# dengenver4_0.net
KiCad netlist of a schematic drawn in EAGLE
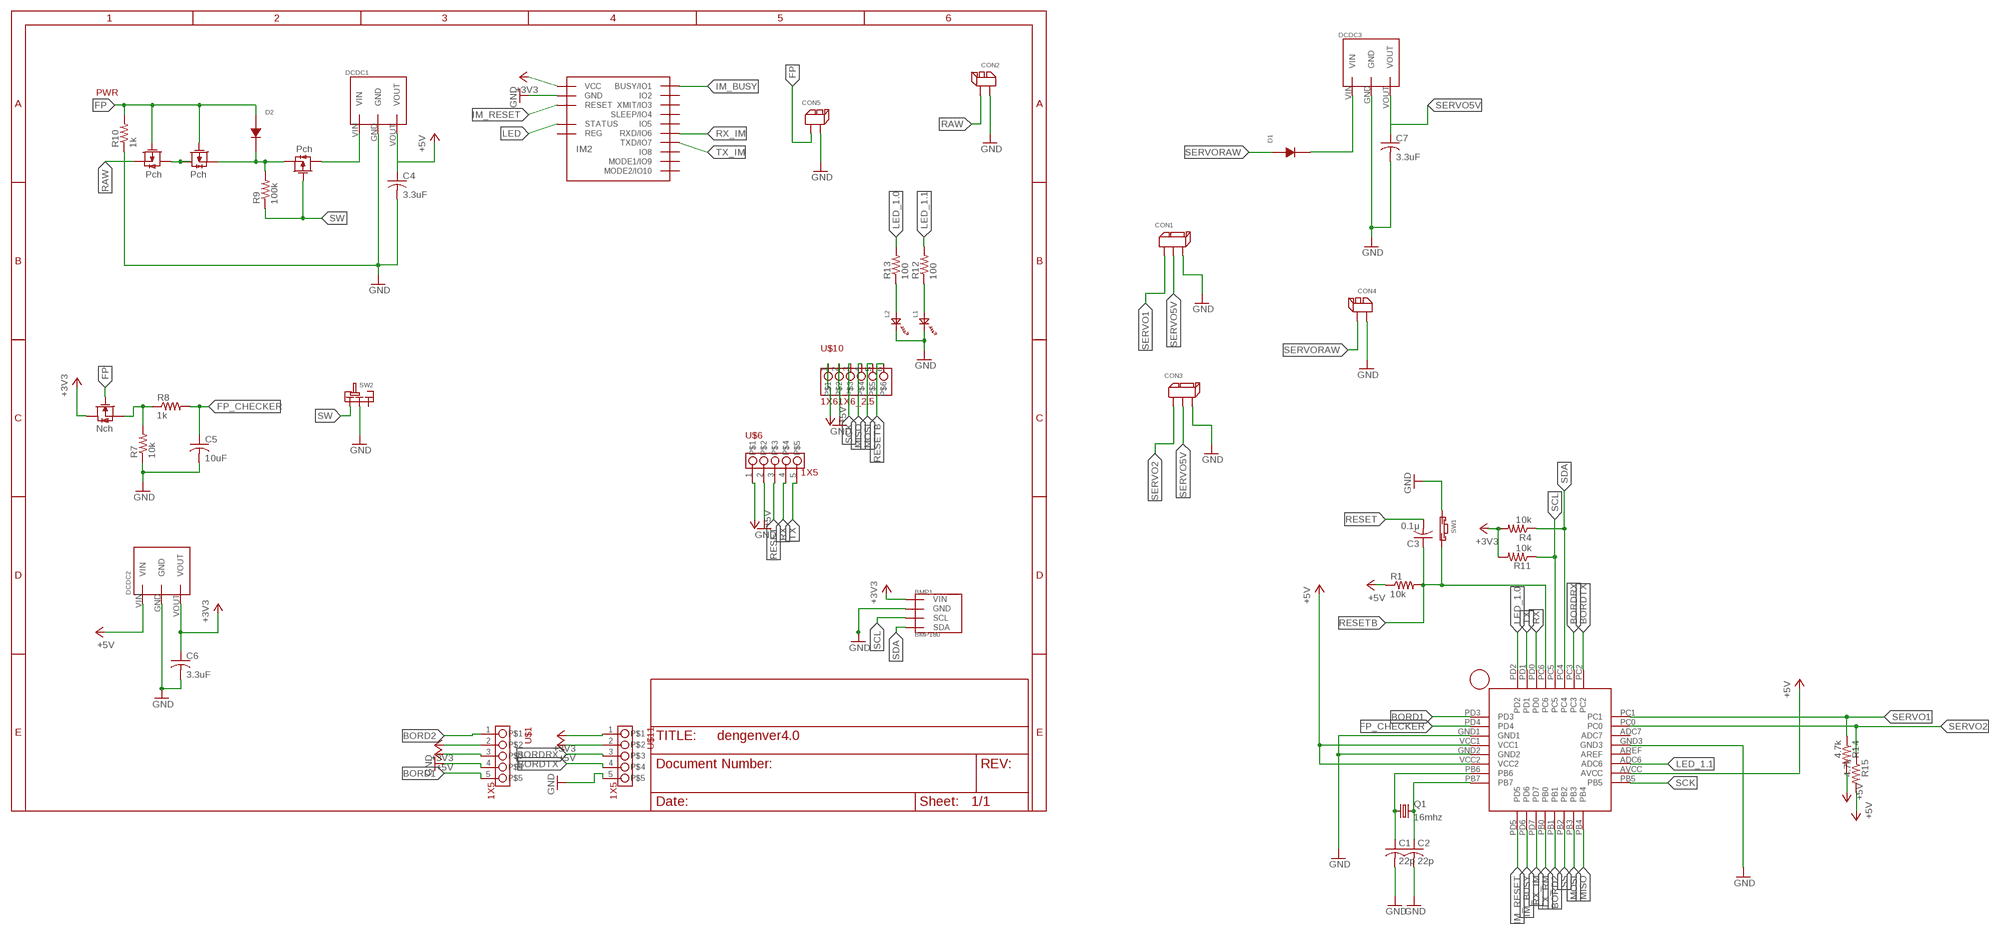
[diagram p0: schematic, sheet 1]

(export (version "E")
  (design (tool "Eeschema 10.0.6"))
  (components
    (comp (ref "BMP1")
      (value "BMP180")
      (footprint "eagle-import:GY-68")
      (libsource (lib "eagle-import") (part "BMP180"))
    )
    (comp (ref "C1")
      (value "22p")
      (footprint "eagle-import:C1608")
      (libsource (lib "eagle-import") (part "C-USC1608"))
    )
    (comp (ref "C2")
      (value "22p")
      (footprint "eagle-import:C1608")
      (libsource (lib "eagle-import") (part "C-USC1608"))
    )
    (comp (ref "C3")
      (value "0.1μ")
      (footprint "eagle-import:C1608")
      (libsource (lib "eagle-import") (part "C-USC1608"))
    )
    (comp (ref "C4")
      (value "3.3uF")
      (footprint "eagle-import:C1608")
      (libsource (lib "eagle-import") (part "C-USC1608"))
    )
    (comp (ref "C5")
      (value "10uF")
      (footprint "eagle-import:C1608")
      (libsource (lib "eagle-import") (part "C-USC1608"))
    )
    (comp (ref "C6")
      (value "3.3uF")
      (footprint "eagle-import:C1608")
      (libsource (lib "eagle-import") (part "C-USC1608"))
    )
    (comp (ref "C7")
      (value "3.3uF")
      (footprint "eagle-import:C0603")
      (libsource (lib "eagle-import") (part "C-USC0603"))
    )
    (comp (ref "CON1")
      (value "3PIN")
      (footprint "eagle-import:3PIN")
      (libsource (lib "eagle-import") (part "3PIN"))
    )
    (comp (ref "CON2")
      (value "2PIN")
      (footprint "eagle-import:2PIN")
      (libsource (lib "eagle-import") (part "2PIN"))
    )
    (comp (ref "CON3")
      (value "3PIN")
      (footprint "eagle-import:3PIN")
      (libsource (lib "eagle-import") (part "3PIN"))
    )
    (comp (ref "CON4")
      (value "2PIN")
      (footprint "eagle-import:2PIN")
      (libsource (lib "eagle-import") (part "2PIN"))
    )
    (comp (ref "CON5")
      (value "2PIN")
      (footprint "eagle-import:2PIN")
      (libsource (lib "eagle-import") (part "2PIN"))
    )
    (comp (ref "D1")
      (value "1W4148W")
      (footprint "eagle-import:SOD-123")
      (libsource (lib "eagle-import") (part "1W4148W"))
    )
    (comp (ref "D2")
      (value "1W4148W")
      (footprint "eagle-import:SOD-123")
      (libsource (lib "eagle-import") (part "1W4148W"))
    )
    (comp (ref "DCDC1")
      (value "5V1A_M78AR05-1")
      (footprint "eagle-import:5V1A_M78AR05-1")
      (libsource (lib "eagle-import") (part "5V1A_M78AR05-1"))
    )
    (comp (ref "DCDC2")
      (value "3.3V1A_M78AR033-1")
      (footprint "eagle-import:3.3V1A_M78AR033-1")
      (libsource (lib "eagle-import") (part "3.3V1A_M78AR033-1"))
    )
    (comp (ref "DCDC3")
      (value "5V1A_M78AR05-1")
      (footprint "eagle-import:5V1A_M78AR05-1")
      (libsource (lib "eagle-import") (part "5V1A_M78AR05-1"))
    )
    (comp (ref "IM2")
      (value "IM920_IM920C")
      (footprint "eagle-import:IM920_IM920C")
      (libsource (lib "eagle-import") (part "IM920_IM920C"))
    )
    (comp (ref "L1")
      (value "OSXX1608C1A")
      (footprint "eagle-import:OSXX1608C1A")
      (libsource (lib "eagle-import") (part "OSXX1608C1A"))
    )
    (comp (ref "L2")
      (value "OSXX1608C1A")
      (footprint "eagle-import:OSXX1608C1A")
      (libsource (lib "eagle-import") (part "OSXX1608C1A"))
    )
    (comp (ref "Q1")
      (value "16mhz")
      (footprint "eagle-import:HC49UP")
      (libsource (lib "eagle-import") (part "CRYSTALHC49UP"))
    )
    (comp (ref "R1")
      (value "10k")
      (footprint "eagle-import:R0603")
      (libsource (lib "eagle-import") (part "R-US_R0603"))
    )
    (comp (ref "R4")
      (value "10k")
      (footprint "eagle-import:R0603")
      (libsource (lib "eagle-import") (part "R-US_R0603"))
    )
    (comp (ref "R7")
      (value "10k")
      (footprint "eagle-import:R0603")
      (libsource (lib "eagle-import") (part "R-US_R0603"))
    )
    (comp (ref "R8")
      (value "1k")
      (footprint "eagle-import:R0603")
      (libsource (lib "eagle-import") (part "R-US_R0603"))
    )
    (comp (ref "R9")
      (value "100k")
      (footprint "eagle-import:R0603")
      (libsource (lib "eagle-import") (part "R-US_R0603"))
    )
    (comp (ref "R10")
      (value "1k")
      (footprint "eagle-import:R0603")
      (libsource (lib "eagle-import") (part "R-US_R0603"))
    )
    (comp (ref "R11")
      (value "10k")
      (footprint "eagle-import:R0603")
      (libsource (lib "eagle-import") (part "R-US_R0603"))
    )
    (comp (ref "R12")
      (value "100")
      (footprint "eagle-import:R0603")
      (libsource (lib "eagle-import") (part "R-US_R0603"))
    )
    (comp (ref "R13")
      (value "100")
      (footprint "eagle-import:R0603")
      (libsource (lib "eagle-import") (part "R-US_R0603"))
    )
    (comp (ref "R14")
      (value "4.7k")
      (footprint "eagle-import:R0603")
      (libsource (lib "eagle-import") (part "R-US_R0603"))
    )
    (comp (ref "R15")
      (value "4.7k")
      (footprint "eagle-import:R0603")
      (libsource (lib "eagle-import") (part "R-US_R0603"))
    )
    (comp (ref "SW1")
      (value "TVAF06-A020B-R")
      (footprint "eagle-import:TVAF06-A020B-R")
      (libsource (lib "eagle-import") (part "TVAF06-A020B-R"))
    )
    (comp (ref "SW2")
      (value "SRIDE_SWITCH")
      (footprint "eagle-import:SRIDE_SWITCH")
      (libsource (lib "eagle-import") (part "SRIDE_SWITCH"))
    )
    (comp (ref "U$1")
      (value "1X5")
      (footprint "eagle-import:HDRVR5W64P254_1X5_1310X250X865B")
      (libsource (lib "eagle-import") (part "1X5"))
    )
    (comp (ref "U$2")
      (value "2SJ681-PCH")
      (footprint "eagle-import:2SJ681")
      (libsource (lib "eagle-import") (part "2SJ681-PCH"))
    )
    (comp (ref "U$3")
      (value "2SK4017-NCH")
      (footprint "eagle-import:2SK4017")
      (libsource (lib "eagle-import") (part "2SK4017-NCH"))
    )
    (comp (ref "U$4")
      (value "2SJ681-PCH")
      (footprint "eagle-import:2SJ681")
      (libsource (lib "eagle-import") (part "2SJ681-PCH"))
    )
    (comp (ref "U$5")
      (value "2SJ681-PCH")
      (footprint "eagle-import:2SJ681")
      (libsource (lib "eagle-import") (part "2SJ681-PCH"))
    )
    (comp (ref "U$6")
      (value "1X5")
      (footprint "eagle-import:HDRVR5W64P254_1X5_1310X250X865B")
      (libsource (lib "eagle-import") (part "1X5"))
    )
    (comp (ref "U$8")
      (value "ATMEGA328P-AU")
      (footprint "eagle-import:QFP80P900X900X120-32N")
      (libsource (lib "eagle-import") (part "ATMEGA328P-AU"))
    )
    (comp (ref "U$10")
      (value "1X61X6_2.5")
      (footprint "eagle-import:HDRVR6W64P254_1X6_1564X250X865B")
      (libsource (lib "eagle-import") (part "1X61X6_2.5"))
    )
    (comp (ref "U$11")
      (value "1X5")
      (footprint "eagle-import:HDRVR5W64P254_1X5_1310X250X865B")
      (libsource (lib "eagle-import") (part "1X5"))
    )
  )
  (nets
    (net (code "1") (name "+3V3") (class "Default")
      (node (ref "BMP1") (pin "P1") (pinfunction "VIN_P1") (pintype "bidirectional"))
      (node (ref "C6") (pin "1") (pinfunction "1_1") (pintype "passive"))
      (node (ref "DCDC2") (pin "VOUT") (pinfunction "VOUT_VOUT") (pintype "bidirectional"))
      (node (ref "IM2") (pin "$P17") (pinfunction "VCC_$P17") (pintype "bidirectional"))
      (node (ref "R11") (pin "2") (pinfunction "2_2") (pintype "passive"))
      (node (ref "R4") (pin "2") (pinfunction "2_2") (pintype "passive"))
      (node (ref "U$1") (pin "2") (pinfunction "P$2_2") (pintype "bidirectional"))
      (node (ref "U$11") (pin "1") (pinfunction "P$1_1") (pintype "bidirectional"))
      (node (ref "U$3") (pin "DRAIN") (pinfunction "DRAIN_DRAIN") (pintype "bidirectional"))
    )
    (net (code "2") (name "+5V") (class "Default")
      (node (ref "C4") (pin "1") (pinfunction "1_1") (pintype "passive"))
      (node (ref "DCDC1") (pin "VOUT") (pinfunction "VOUT_VOUT") (pintype "bidirectional"))
      (node (ref "DCDC2") (pin "VIN") (pinfunction "VIN_VIN") (pintype "bidirectional"))
      (node (ref "R1") (pin "1") (pinfunction "1_1") (pintype "passive"))
      (node (ref "R14") (pin "2") (pinfunction "2_2") (pintype "passive"))
      (node (ref "R15") (pin "2") (pinfunction "2_2") (pintype "passive"))
      (node (ref "U$1") (pin "3") (pinfunction "P$3_3") (pintype "bidirectional"))
      (node (ref "U$10") (pin "1") (pinfunction "P$1_1") (pintype "bidirectional"))
      (node (ref "U$11") (pin "2") (pinfunction "P$2_2") (pintype "bidirectional"))
      (node (ref "U$6") (pin "1") (pinfunction "P$1_1") (pintype "bidirectional"))
      (node (ref "U$8") (pin "AVCC") (pinfunction "AVCC_AVCC") (pintype "bidirectional"))
      (node (ref "U$8") (pin "VCC1") (pinfunction "VCC1_VCC1") (pintype "bidirectional"))
      (node (ref "U$8") (pin "VCC2") (pinfunction "VCC2_VCC2") (pintype "bidirectional"))
    )
    (net (code "3") (name "BORD1") (class "Default")
      (node (ref "U$1") (pin "5") (pinfunction "P$5_5") (pintype "bidirectional"))
      (node (ref "U$8") (pin "PD3") (pinfunction "PD3_PD3") (pintype "bidirectional"))
    )
    (net (code "4") (name "BORD2") (class "Default")
      (node (ref "U$1") (pin "1") (pinfunction "P$1_1") (pintype "bidirectional"))
      (node (ref "U$8") (pin "PB1") (pinfunction "PB1_PB1") (pintype "bidirectional"))
    )
    (net (code "5") (name "BORDRX") (class "Default")
      (node (ref "U$11") (pin "3") (pinfunction "P$3_3") (pintype "bidirectional"))
      (node (ref "U$8") (pin "PC3") (pinfunction "PC3_PC3") (pintype "bidirectional"))
    )
    (net (code "6") (name "BORDTX") (class "Default")
      (node (ref "U$11") (pin "4") (pinfunction "P$4_4") (pintype "bidirectional"))
      (node (ref "U$8") (pin "PC2") (pinfunction "PC2_PC2") (pintype "bidirectional"))
    )
    (net (code "7") (name "FP") (class "Default")
      (node (ref "CON5") (pin "P$1") (pinfunction "P$1_P$1") (pintype "bidirectional"))
      (node (ref "D2") (pin "C") (pinfunction "C_C") (pintype "bidirectional"))
      (node (ref "R10") (pin "2") (pinfunction "2_2") (pintype "passive"))
      (node (ref "U$2") (pin "GATE") (pinfunction "GATE_GATE") (pintype "bidirectional"))
      (node (ref "U$3") (pin "GATE") (pinfunction "GATE_GATE") (pintype "bidirectional"))
      (node (ref "U$4") (pin "GATE") (pinfunction "GATE_GATE") (pintype "bidirectional"))
    )
    (net (code "8") (name "FP_CHECKER") (class "Default")
      (node (ref "C5") (pin "1") (pinfunction "1_1") (pintype "passive"))
      (node (ref "R8") (pin "2") (pinfunction "2_2") (pintype "passive"))
      (node (ref "U$8") (pin "PD4") (pinfunction "PD4_PD4") (pintype "bidirectional"))
    )
    (net (code "9") (name "GND") (class "Default")
      (node (ref "BMP1") (pin "P2") (pinfunction "GND_P2") (pintype "bidirectional"))
      (node (ref "C1") (pin "2") (pinfunction "2_2") (pintype "passive"))
      (node (ref "C2") (pin "2") (pinfunction "2_2") (pintype "passive"))
      (node (ref "C4") (pin "2") (pinfunction "2_2") (pintype "passive"))
      (node (ref "C5") (pin "2") (pinfunction "2_2") (pintype "passive"))
      (node (ref "C6") (pin "2") (pinfunction "2_2") (pintype "passive"))
      (node (ref "C7") (pin "2") (pinfunction "2_2") (pintype "passive"))
      (node (ref "CON1") (pin "P$3") (pinfunction "P$3_P$3") (pintype "bidirectional"))
      (node (ref "CON2") (pin "P$1") (pinfunction "P$1_P$1") (pintype "bidirectional"))
      (node (ref "CON3") (pin "P$3") (pinfunction "P$3_P$3") (pintype "bidirectional"))
      (node (ref "CON4") (pin "P$1") (pinfunction "P$1_P$1") (pintype "bidirectional"))
      (node (ref "CON5") (pin "P$2") (pinfunction "P$2_P$2") (pintype "bidirectional"))
      (node (ref "DCDC1") (pin "GND") (pinfunction "GND_GND") (pintype "bidirectional"))
      (node (ref "DCDC2") (pin "GND") (pinfunction "GND_GND") (pintype "bidirectional"))
      (node (ref "DCDC3") (pin "GND") (pinfunction "GND_GND") (pintype "bidirectional"))
      (node (ref "IM2") (pin "$P18") (pinfunction "GND_$P18") (pintype "bidirectional"))
      (node (ref "L1") (pin "CT") (pinfunction "CT_CT") (pintype "bidirectional"))
      (node (ref "L2") (pin "CT") (pinfunction "CT_CT") (pintype "bidirectional"))
      (node (ref "R10") (pin "1") (pinfunction "1_1") (pintype "passive"))
      (node (ref "R7") (pin "1") (pinfunction "1_1") (pintype "passive"))
      (node (ref "SW1") (pin "P$1") (pinfunction "P$1_P$1") (pintype "bidirectional"))
      (node (ref "SW2") (pin "LR") (pinfunction "LR_LR") (pintype "bidirectional"))
      (node (ref "U$1") (pin "4") (pinfunction "P$4_4") (pintype "bidirectional"))
      (node (ref "U$10") (pin "2") (pinfunction "P$2_2") (pintype "bidirectional"))
      (node (ref "U$11") (pin "5") (pinfunction "P$5_5") (pintype "bidirectional"))
      (node (ref "U$6") (pin "2") (pinfunction "P$2_2") (pintype "bidirectional"))
      (node (ref "U$8") (pin "GND1") (pinfunction "GND1_GND1") (pintype "bidirectional"))
      (node (ref "U$8") (pin "GND2") (pinfunction "GND2_GND2") (pintype "bidirectional"))
      (node (ref "U$8") (pin "GND3") (pinfunction "GND3_GND3") (pintype "bidirectional"))
    )
    (net (code "10") (name "IM_BUSY") (class "Default")
      (node (ref "IM2") (pin "$P1") (pinfunction "BUSY/IO1_$P1") (pintype "bidirectional"))
      (node (ref "U$8") (pin "PD6") (pinfunction "PD6_PD6") (pintype "bidirectional"))
    )
    (net (code "11") (name "IM_RESET") (class "Default")
      (node (ref "IM2") (pin "$P19") (pinfunction "RESET_$P19") (pintype "bidirectional"))
      (node (ref "U$8") (pin "PD5") (pinfunction "PD5_PD5") (pintype "bidirectional"))
    )
    (net (code "12") (name "LED") (class "Default")
      (node (ref "IM2") (pin "$P15") (pinfunction "STATUS_$P15") (pintype "bidirectional"))
    )
    (net (code "13") (name "LED_1.0") (class "Default")
      (node (ref "R13") (pin "2") (pinfunction "2_2") (pintype "passive"))
      (node (ref "U$8") (pin "PD2") (pinfunction "PD2_PD2") (pintype "bidirectional"))
    )
    (net (code "14") (name "LED_1.1") (class "Default")
      (node (ref "R12") (pin "2") (pinfunction "2_2") (pintype "passive"))
      (node (ref "U$8") (pin "ADC6") (pinfunction "ADC6_ADC6") (pintype "bidirectional"))
    )
    (net (code "15") (name "MISO") (class "Default")
      (node (ref "U$10") (pin "4") (pinfunction "P$4_4") (pintype "bidirectional"))
      (node (ref "U$8") (pin "PB4") (pinfunction "PB4_PB4") (pintype "bidirectional"))
    )
    (net (code "16") (name "MOSI") (class "Default")
      (node (ref "U$10") (pin "5") (pinfunction "P$5_5") (pintype "bidirectional"))
      (node (ref "U$8") (pin "PB3") (pinfunction "PB3_PB3") (pintype "bidirectional"))
    )
    (net (code "17") (name "Net-(C1-Pad1)") (class "Default")
      (node (ref "C1") (pin "1") (pinfunction "1_1") (pintype "passive"))
      (node (ref "Q1") (pin "1") (pinfunction "1_1") (pintype "passive"))
      (node (ref "U$8") (pin "PB6") (pinfunction "PB6_PB6") (pintype "bidirectional"))
    )
    (net (code "18") (name "Net-(C2-Pad1)") (class "Default")
      (node (ref "C2") (pin "1") (pinfunction "1_1") (pintype "passive"))
      (node (ref "Q1") (pin "2") (pinfunction "2_2") (pintype "passive"))
      (node (ref "U$8") (pin "PB7") (pinfunction "PB7_PB7") (pintype "bidirectional"))
    )
    (net (code "19") (name "Net-(D2-PadA)") (class "Default")
      (node (ref "D2") (pin "A") (pinfunction "A_A") (pintype "bidirectional"))
      (node (ref "R9") (pin "2") (pinfunction "2_2") (pintype "passive"))
      (node (ref "U$4") (pin "SOURCE") (pinfunction "SOURCE_SOURCE") (pintype "bidirectional"))
      (node (ref "U$5") (pin "SOURCE") (pinfunction "SOURCE_SOURCE") (pintype "bidirectional"))
    )
    (net (code "20") (name "Net-(DCDC1-PadVIN)") (class "Default")
      (node (ref "DCDC1") (pin "VIN") (pinfunction "VIN_VIN") (pintype "bidirectional"))
      (node (ref "U$5") (pin "DRAIN") (pinfunction "DRAIN_DRAIN") (pintype "bidirectional"))
    )
    (net (code "21") (name "Net-(L1-PadAN)") (class "Default")
      (node (ref "L1") (pin "AN") (pinfunction "AN_AN") (pintype "bidirectional"))
      (node (ref "R12") (pin "1") (pinfunction "1_1") (pintype "passive"))
    )
    (net (code "22") (name "Net-(L2-PadAN)") (class "Default")
      (node (ref "L2") (pin "AN") (pinfunction "AN_AN") (pintype "bidirectional"))
      (node (ref "R13") (pin "1") (pinfunction "1_1") (pintype "passive"))
    )
    (net (code "23") (name "Net-(R7-Pad2)") (class "Default")
      (node (ref "R7") (pin "2") (pinfunction "2_2") (pintype "passive"))
      (node (ref "R8") (pin "1") (pinfunction "1_1") (pintype "passive"))
      (node (ref "U$3") (pin "SOURCE") (pinfunction "SOURCE_SOURCE") (pintype "bidirectional"))
    )
    (net (code "24") (name "Net-(U$2-PadDRAIN)") (class "Default")
      (node (ref "U$2") (pin "DRAIN") (pinfunction "DRAIN_DRAIN") (pintype "bidirectional"))
      (node (ref "U$4") (pin "DRAIN") (pinfunction "DRAIN_DRAIN") (pintype "bidirectional"))
    )
    (net (code "25") (name "RAW") (class "Default")
      (node (ref "CON2") (pin "P$2") (pinfunction "P$2_P$2") (pintype "bidirectional"))
      (node (ref "U$2") (pin "SOURCE") (pinfunction "SOURCE_SOURCE") (pintype "bidirectional"))
    )
    (net (code "26") (name "RESET") (class "Default")
      (node (ref "C3") (pin "2") (pinfunction "2_2") (pintype "passive"))
      (node (ref "U$6") (pin "3") (pinfunction "P$3_3") (pintype "bidirectional"))
    )
    (net (code "27") (name "RESETB") (class "Default")
      (node (ref "C3") (pin "1") (pinfunction "1_1") (pintype "passive"))
      (node (ref "R1") (pin "2") (pinfunction "2_2") (pintype "passive"))
      (node (ref "SW1") (pin "P$2") (pinfunction "P$2_P$2") (pintype "bidirectional"))
      (node (ref "U$10") (pin "6") (pinfunction "P$6_6") (pintype "bidirectional"))
      (node (ref "U$8") (pin "PC6") (pinfunction "PC6_PC6") (pintype "bidirectional"))
    )
    (net (code "28") (name "RX") (class "Default")
      (node (ref "U$6") (pin "4") (pinfunction "P$4_4") (pintype "bidirectional"))
      (node (ref "U$8") (pin "PD0") (pinfunction "PD0_PD0") (pintype "bidirectional"))
    )
    (net (code "29") (name "RX_IM") (class "Default")
      (node (ref "IM2") (pin "$P6") (pinfunction "RXD/IO6_$P6") (pintype "bidirectional"))
      (node (ref "U$8") (pin "PD7") (pinfunction "PD7_PD7") (pintype "bidirectional"))
    )
    (net (code "30") (name "SCK") (class "Default")
      (node (ref "U$10") (pin "3") (pinfunction "P$3_3") (pintype "bidirectional"))
      (node (ref "U$8") (pin "PB5") (pinfunction "PB5_PB5") (pintype "bidirectional"))
    )
    (net (code "31") (name "SCL") (class "Default")
      (node (ref "BMP1") (pin "P3") (pinfunction "SCL_P3") (pintype "bidirectional"))
      (node (ref "R11") (pin "1") (pinfunction "1_1") (pintype "passive"))
      (node (ref "U$8") (pin "PC5") (pinfunction "PC5_PC5") (pintype "bidirectional"))
    )
    (net (code "32") (name "SDA") (class "Default")
      (node (ref "BMP1") (pin "P4") (pinfunction "SDA_P4") (pintype "bidirectional"))
      (node (ref "R4") (pin "1") (pinfunction "1_1") (pintype "passive"))
      (node (ref "U$8") (pin "PC4") (pinfunction "PC4_PC4") (pintype "bidirectional"))
    )
    (net (code "33") (name "SERVO1") (class "Default")
      (node (ref "CON1") (pin "P$1") (pinfunction "P$1_P$1") (pintype "bidirectional"))
      (node (ref "R14") (pin "1") (pinfunction "1_1") (pintype "passive"))
      (node (ref "U$8") (pin "PC1") (pinfunction "PC1_PC1") (pintype "bidirectional"))
    )
    (net (code "34") (name "SERVO2") (class "Default")
      (node (ref "CON3") (pin "P$1") (pinfunction "P$1_P$1") (pintype "bidirectional"))
      (node (ref "R15") (pin "1") (pinfunction "1_1") (pintype "passive"))
      (node (ref "U$8") (pin "PC0") (pinfunction "PC0_PC0") (pintype "bidirectional"))
    )
    (net (code "35") (name "SERVO5V") (class "Default")
      (node (ref "C7") (pin "1") (pinfunction "1_1") (pintype "passive"))
      (node (ref "CON1") (pin "P$2") (pinfunction "P$2_P$2") (pintype "bidirectional"))
      (node (ref "CON3") (pin "P$2") (pinfunction "P$2_P$2") (pintype "bidirectional"))
      (node (ref "DCDC3") (pin "VOUT") (pinfunction "VOUT_VOUT") (pintype "bidirectional"))
    )
    (net (code "36") (name "SERVORAW") (class "Default")
      (node (ref "CON4") (pin "P$2") (pinfunction "P$2_P$2") (pintype "bidirectional"))
      (node (ref "D1") (pin "A") (pinfunction "A_A") (pintype "bidirectional"))
      (node (ref "DCDC3") (pin "VIN") (pinfunction "VIN_VIN") (pintype "bidirectional"))
    )
    (net (code "37") (name "SS") (class "Default")
      (node (ref "U$8") (pin "PB2") (pinfunction "PB2_PB2") (pintype "bidirectional"))
    )
    (net (code "38") (name "SW") (class "Default")
      (node (ref "R9") (pin "1") (pinfunction "1_1") (pintype "passive"))
      (node (ref "SW2") (pin "L") (pinfunction "L_L") (pintype "bidirectional"))
      (node (ref "U$5") (pin "GATE") (pinfunction "GATE_GATE") (pintype "bidirectional"))
    )
    (net (code "39") (name "TX") (class "Default")
      (node (ref "U$6") (pin "5") (pinfunction "P$5_5") (pintype "bidirectional"))
      (node (ref "U$8") (pin "PD1") (pinfunction "PD1_PD1") (pintype "bidirectional"))
    )
    (net (code "40") (name "TX_IM") (class "Default")
      (node (ref "IM2") (pin "$P7") (pinfunction "TXD/IO7_$P7") (pintype "bidirectional"))
    )
    (net (code "41") (name "TX_RM") (class "Default")
      (node (ref "U$8") (pin "PB0") (pinfunction "PB0_PB0") (pintype "bidirectional"))
    )
    (net (code "42") (name "unconnected-(D1-PadC)") (class "Default")
      (node (ref "D1") (pin "C") (pinfunction "C_C") (pintype "bidirectional"))
    )
    (net (code "43") (name "unconnected-(IM2-IO2-Pad$P2)") (class "Default")
      (node (ref "IM2") (pin "$P2") (pinfunction "IO2_$P2") (pintype "bidirectional"))
    )
    (net (code "44") (name "unconnected-(IM2-IO5-Pad$P5)") (class "Default")
      (node (ref "IM2") (pin "$P5") (pinfunction "IO5_$P5") (pintype "bidirectional"))
    )
    (net (code "45") (name "unconnected-(IM2-IO8-Pad$P8)") (class "Default")
      (node (ref "IM2") (pin "$P8") (pinfunction "IO8_$P8") (pintype "bidirectional"))
    )
    (net (code "46") (name "unconnected-(IM2-MODE1{slash}IO9-Pad$P9)") (class "Default")
      (node (ref "IM2") (pin "$P9") (pinfunction "MODE1/IO9_$P9") (pintype "bidirectional"))
    )
    (net (code "47") (name "unconnected-(IM2-MODE2{slash}IO10-Pad$P10)") (class "Default")
      (node (ref "IM2") (pin "$P10") (pinfunction "MODE2/IO10_$P10") (pintype "bidirectional"))
    )
    (net (code "48") (name "unconnected-(IM2-REG-Pad$P16)") (class "Default")
      (node (ref "IM2") (pin "$P16") (pinfunction "REG_$P16") (pintype "bidirectional"))
    )
    (net (code "49") (name "unconnected-(IM2-SLEEP{slash}IO4-Pad$P4)") (class "Default")
      (node (ref "IM2") (pin "$P4") (pinfunction "SLEEP/IO4_$P4") (pintype "bidirectional"))
    )
    (net (code "50") (name "unconnected-(IM2-XMIT{slash}IO3-Pad$P3)") (class "Default")
      (node (ref "IM2") (pin "$P3") (pinfunction "XMIT/IO3_$P3") (pintype "bidirectional"))
    )
    (net (code "51") (name "unconnected-(SW2-PadR)") (class "Default")
      (node (ref "SW2") (pin "R") (pinfunction "R_R") (pintype "bidirectional"))
    )
    (net (code "52") (name "unconnected-(U$8-PadADC7)") (class "Default")
      (node (ref "U$8") (pin "ADC7") (pinfunction "ADC7_ADC7") (pintype "bidirectional"))
    )
    (net (code "53") (name "unconnected-(U$8-PadAREF)") (class "Default")
      (node (ref "U$8") (pin "AREF") (pinfunction "AREF_AREF") (pintype "bidirectional"))
    )
  )
)
